# CloudF4Block_MicroPython.net
KiCad netlist of a schematic drawn in Altium Designer
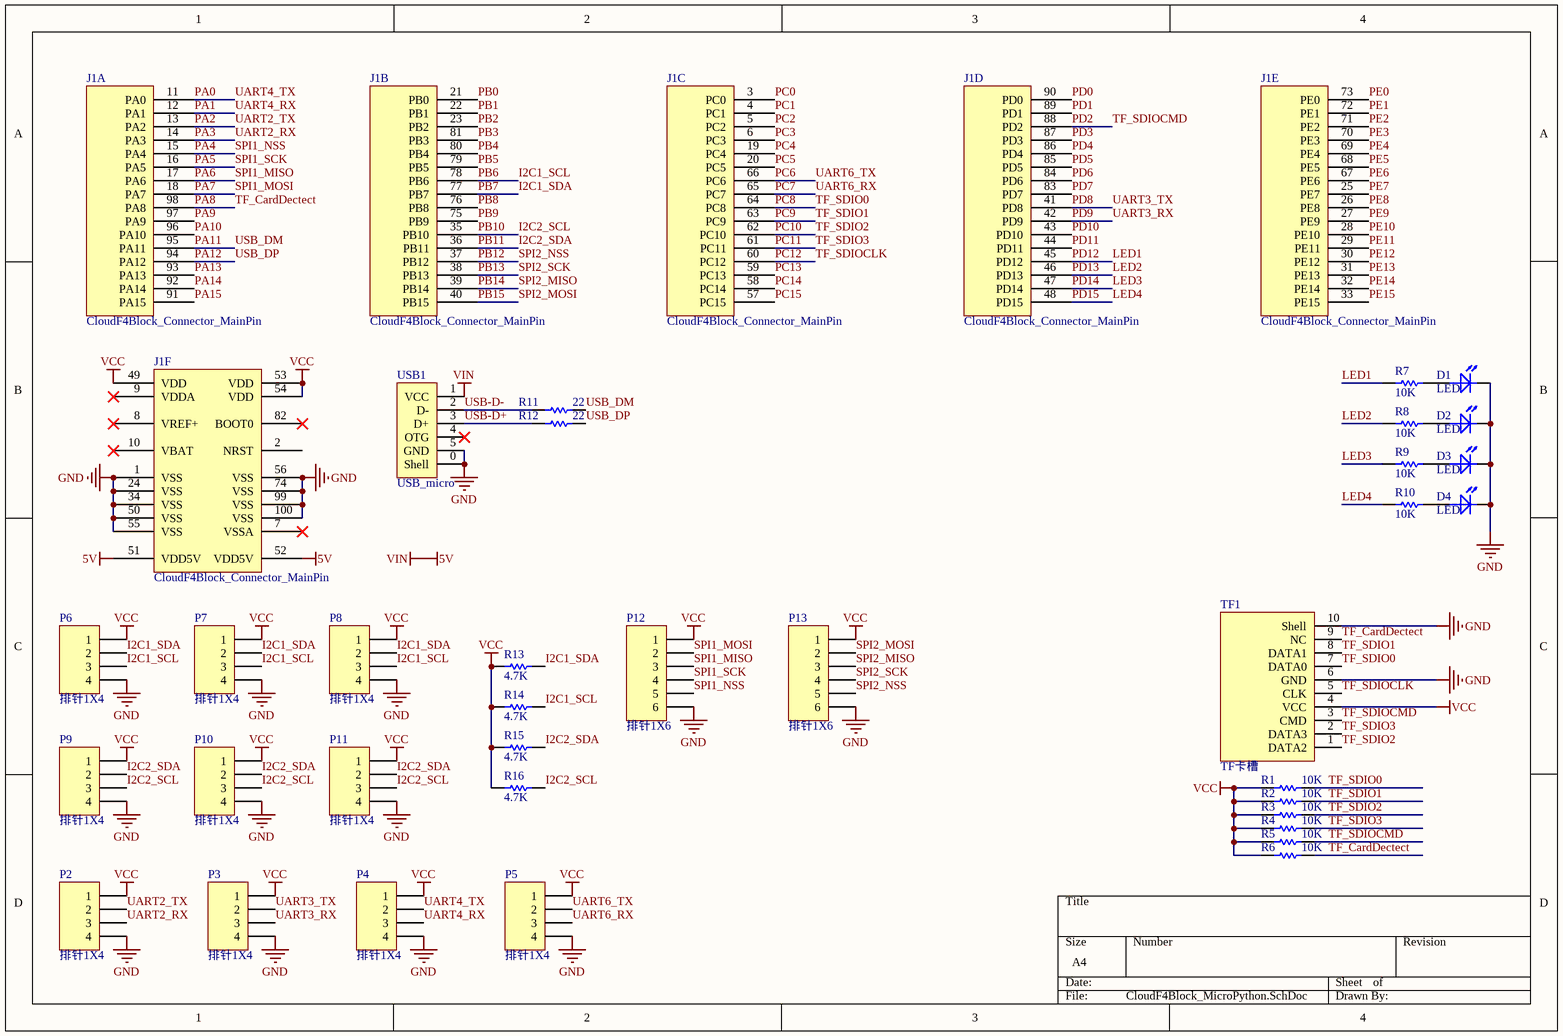
[diagram p0: CloudF4Block_MicroPython.SchDoc]

(export (version "E")
  (design (tool "Eeschema 10.0.6"))
  (components
    (comp (ref "D1")
      (value "LED")
      (footprint "0603LED_RED")
      (libsource (lib "Cloud_AD_Integrated") (part "LED"))
    )
    (comp (ref "D2")
      (value "LED")
      (footprint "0603LED_GREEN")
      (libsource (lib "Cloud_AD_Integrated") (part "LED"))
    )
    (comp (ref "D3")
      (value "LED")
      (footprint "0603LED_ORANGE")
      (libsource (lib "Cloud_AD_Integrated") (part "LED"))
    )
    (comp (ref "D4")
      (value "LED")
      (footprint "0603LED_YELLOW")
      (libsource (lib "Cloud_AD_Integrated") (part "LED"))
    )
    (comp (ref "J1")
      (value "CloudF4Block_Connector_MainPin")
      (footprint "CloudF4BlockConnector")
      (libsource (lib "Cloud_AD_Integrated") (part "CloudF4Block_Connector_MainPin"))
    )
    (comp (ref "P2")
      (value "排针1X4")
      (footprint "IDC1x4-2.54")
      (libsource (lib "Cloud_AD_Integrated") (part "排针1X4"))
    )
    (comp (ref "P3")
      (value "排针1X4")
      (footprint "IDC1x4-2.54")
      (libsource (lib "Cloud_AD_Integrated") (part "排针1X4"))
    )
    (comp (ref "P4")
      (value "排针1X4")
      (footprint "IDC1x4-2.54")
      (libsource (lib "Cloud_AD_Integrated") (part "排针1X4"))
    )
    (comp (ref "P5")
      (value "排针1X4")
      (footprint "IDC1x4-2.54")
      (libsource (lib "Cloud_AD_Integrated") (part "排针1X4"))
    )
    (comp (ref "P6")
      (value "排针1X4")
      (footprint "IDC1x4-2.54")
      (libsource (lib "Cloud_AD_Integrated") (part "排针1X4"))
    )
    (comp (ref "P7")
      (value "排针1X4")
      (footprint "IDC1x4-2.54")
      (libsource (lib "Cloud_AD_Integrated") (part "排针1X4"))
    )
    (comp (ref "P8")
      (value "排针1X4")
      (footprint "IDC1x4-2.54")
      (libsource (lib "Cloud_AD_Integrated") (part "排针1X4"))
    )
    (comp (ref "P9")
      (value "排针1X4")
      (footprint "IDC1x4-2.54")
      (libsource (lib "Cloud_AD_Integrated") (part "排针1X4"))
    )
    (comp (ref "P10")
      (value "排针1X4")
      (footprint "IDC1x4-2.54")
      (libsource (lib "Cloud_AD_Integrated") (part "排针1X4"))
    )
    (comp (ref "P11")
      (value "排针1X4")
      (footprint "IDC1x4-2.54")
      (libsource (lib "Cloud_AD_Integrated") (part "排针1X4"))
    )
    (comp (ref "P12")
      (value "排针1X6")
      (footprint "IDC1x6-2.54")
      (libsource (lib "Cloud_AD_Integrated") (part "排针1X6"))
    )
    (comp (ref "P13")
      (value "排针1X6")
      (footprint "IDC1x6-2.54")
      (libsource (lib "Cloud_AD_Integrated") (part "排针1X6"))
    )
    (comp (ref "R1")
      (value "10K")
      (footprint "R-0603")
      (fields (field (name "Comment") "RES"))
      (libsource (lib "Cloud_AD_Integrated") (part "RES"))
    )
    (comp (ref "R2")
      (value "10K")
      (footprint "R-0603")
      (fields (field (name "Comment") "RES"))
      (libsource (lib "Cloud_AD_Integrated") (part "RES"))
    )
    (comp (ref "R3")
      (value "10K")
      (footprint "R-0603")
      (fields (field (name "Comment") "RES"))
      (libsource (lib "Cloud_AD_Integrated") (part "RES"))
    )
    (comp (ref "R4")
      (value "10K")
      (footprint "R-0603")
      (fields (field (name "Comment") "RES"))
      (libsource (lib "Cloud_AD_Integrated") (part "RES"))
    )
    (comp (ref "R5")
      (value "10K")
      (footprint "R-0603")
      (fields (field (name "Comment") "RES"))
      (libsource (lib "Cloud_AD_Integrated") (part "RES"))
    )
    (comp (ref "R6")
      (value "10K")
      (footprint "R-0603")
      (fields (field (name "Comment") "RES"))
      (libsource (lib "Cloud_AD_Integrated") (part "RES"))
    )
    (comp (ref "R7")
      (value "10K")
      (footprint "R-0603")
      (fields (field (name "Comment") "RES"))
      (libsource (lib "Cloud_AD_Integrated") (part "RES"))
    )
    (comp (ref "R8")
      (value "10K")
      (footprint "R-0603")
      (fields (field (name "Comment") "RES"))
      (libsource (lib "Cloud_AD_Integrated") (part "RES"))
    )
    (comp (ref "R9")
      (value "10K")
      (footprint "R-0603")
      (fields (field (name "Comment") "RES"))
      (libsource (lib "Cloud_AD_Integrated") (part "RES"))
    )
    (comp (ref "R10")
      (value "10K")
      (footprint "R-0603")
      (fields (field (name "Comment") "RES"))
      (libsource (lib "Cloud_AD_Integrated") (part "RES"))
    )
    (comp (ref "R11")
      (value "22")
      (footprint "R-0603")
      (fields (field (name "Comment") "RES"))
      (libsource (lib "Cloud_AD_Integrated") (part "RES"))
    )
    (comp (ref "R12")
      (value "22")
      (footprint "R-0603")
      (fields (field (name "Comment") "RES"))
      (libsource (lib "Cloud_AD_Integrated") (part "RES"))
    )
    (comp (ref "R13")
      (value "4.7K")
      (footprint "R-0603")
      (fields (field (name "Comment") "RES"))
      (libsource (lib "Cloud_AD_Integrated") (part "RES"))
    )
    (comp (ref "R14")
      (value "4.7K")
      (footprint "R-0603")
      (fields (field (name "Comment") "RES"))
      (libsource (lib "Cloud_AD_Integrated") (part "RES"))
    )
    (comp (ref "R15")
      (value "4.7K")
      (footprint "R-0603")
      (fields (field (name "Comment") "RES"))
      (libsource (lib "Cloud_AD_Integrated") (part "RES"))
    )
    (comp (ref "R16")
      (value "4.7K")
      (footprint "R-0603")
      (fields (field (name "Comment") "RES"))
      (libsource (lib "Cloud_AD_Integrated") (part "RES"))
    )
    (comp (ref "TF1")
      (value "TF卡槽")
      (footprint "TF_Card")
      (libsource (lib "Cloud_AD_Integrated") (part "TF卡槽"))
    )
    (comp (ref "USB1")
      (value "USB_micro")
      (footprint "USB-MICRO")
      (libsource (lib "Cloud_AD_Integrated") (part "USB_micro"))
    )
  )
  (nets
    (net (code "1") (name "/I2C1_SCL") (class "Default")
      (node (ref "J1") (pin "78") (pinfunction "PB6_78") (pintype "passive"))
      (node (ref "P6") (pin "3") (pinfunction "3_3") (pintype "passive"))
      (node (ref "P7") (pin "3") (pinfunction "3_3") (pintype "passive"))
      (node (ref "P8") (pin "3") (pinfunction "3_3") (pintype "passive"))
      (node (ref "R14") (pin "2") (pinfunction "2_2") (pintype "passive"))
    )
    (net (code "2") (name "/I2C1_SDA") (class "Default")
      (node (ref "J1") (pin "77") (pinfunction "PB7_77") (pintype "passive"))
      (node (ref "P6") (pin "2") (pinfunction "2_2") (pintype "passive"))
      (node (ref "P7") (pin "2") (pinfunction "2_2") (pintype "passive"))
      (node (ref "P8") (pin "2") (pinfunction "2_2") (pintype "passive"))
      (node (ref "R13") (pin "2") (pinfunction "2_2") (pintype "passive"))
    )
    (net (code "3") (name "/I2C2_SCL") (class "Default")
      (node (ref "J1") (pin "35") (pinfunction "PB10_35") (pintype "passive"))
      (node (ref "P10") (pin "3") (pinfunction "3_3") (pintype "passive"))
      (node (ref "P11") (pin "3") (pinfunction "3_3") (pintype "passive"))
      (node (ref "P9") (pin "3") (pinfunction "3_3") (pintype "passive"))
      (node (ref "R16") (pin "2") (pinfunction "2_2") (pintype "passive"))
    )
    (net (code "4") (name "/I2C2_SDA") (class "Default")
      (node (ref "J1") (pin "36") (pinfunction "PB11_36") (pintype "passive"))
      (node (ref "P10") (pin "2") (pinfunction "2_2") (pintype "passive"))
      (node (ref "P11") (pin "2") (pinfunction "2_2") (pintype "passive"))
      (node (ref "P9") (pin "2") (pinfunction "2_2") (pintype "passive"))
      (node (ref "R15") (pin "2") (pinfunction "2_2") (pintype "passive"))
    )
    (net (code "5") (name "/LED1") (class "Default")
      (node (ref "J1") (pin "45") (pinfunction "PD12_45") (pintype "passive"))
      (node (ref "R7") (pin "2") (pinfunction "2_2") (pintype "passive"))
    )
    (net (code "6") (name "/LED2") (class "Default")
      (node (ref "J1") (pin "46") (pinfunction "PD13_46") (pintype "passive"))
      (node (ref "R8") (pin "2") (pinfunction "2_2") (pintype "passive"))
    )
    (net (code "7") (name "/LED3") (class "Default")
      (node (ref "J1") (pin "47") (pinfunction "PD14_47") (pintype "passive"))
      (node (ref "R9") (pin "2") (pinfunction "2_2") (pintype "passive"))
    )
    (net (code "8") (name "/LED4") (class "Default")
      (node (ref "J1") (pin "48") (pinfunction "PD15_48") (pintype "passive"))
      (node (ref "R10") (pin "2") (pinfunction "2_2") (pintype "passive"))
    )
    (net (code "9") (name "/PA0") (class "Default")
      (node (ref "J1") (pin "11") (pinfunction "PA0_11") (pintype "passive"))
      (node (ref "P4") (pin "2") (pinfunction "2_2") (pintype "passive"))
    )
    (net (code "10") (name "/PA1") (class "Default")
      (node (ref "J1") (pin "12") (pinfunction "PA1_12") (pintype "passive"))
      (node (ref "P4") (pin "3") (pinfunction "3_3") (pintype "passive"))
    )
    (net (code "11") (name "/PA2") (class "Default")
      (node (ref "J1") (pin "13") (pinfunction "PA2_13") (pintype "passive"))
      (node (ref "P2") (pin "2") (pinfunction "2_2") (pintype "passive"))
    )
    (net (code "12") (name "/PA3") (class "Default")
      (node (ref "J1") (pin "14") (pinfunction "PA3_14") (pintype "passive"))
      (node (ref "P2") (pin "3") (pinfunction "3_3") (pintype "passive"))
    )
    (net (code "13") (name "/PA4") (class "Default")
      (node (ref "J1") (pin "15") (pinfunction "PA4_15") (pintype "passive"))
      (node (ref "P12") (pin "5") (pinfunction "5_5") (pintype "passive"))
    )
    (net (code "14") (name "/PA5") (class "Default")
      (node (ref "J1") (pin "16") (pinfunction "PA5_16") (pintype "passive"))
      (node (ref "P12") (pin "4") (pinfunction "4_4") (pintype "passive"))
    )
    (net (code "15") (name "/PA6") (class "Default")
      (node (ref "J1") (pin "17") (pinfunction "PA6_17") (pintype "passive"))
      (node (ref "P12") (pin "3") (pinfunction "3_3") (pintype "passive"))
    )
    (net (code "16") (name "/PA7") (class "Default")
      (node (ref "J1") (pin "18") (pinfunction "PA7_18") (pintype "passive"))
      (node (ref "P12") (pin "2") (pinfunction "2_2") (pintype "passive"))
    )
    (net (code "17") (name "/PA8") (class "Default")
      (node (ref "J1") (pin "98") (pinfunction "PA8_98") (pintype "passive"))
      (node (ref "R6") (pin "2") (pinfunction "2_2") (pintype "passive"))
      (node (ref "TF1") (pin "9") (pinfunction "NC_9") (pintype "passive"))
    )
    (net (code "18") (name "/PA9") (class "Default")
      (node (ref "J1") (pin "97") (pinfunction "PA9_97") (pintype "passive"))
    )
    (net (code "19") (name "/PA10") (class "Default")
      (node (ref "J1") (pin "96") (pinfunction "PA10_96") (pintype "passive"))
    )
    (net (code "20") (name "/PA11") (class "Default")
      (node (ref "J1") (pin "95") (pinfunction "PA11_95") (pintype "passive"))
      (node (ref "R11") (pin "1") (pinfunction "1_1") (pintype "passive"))
    )
    (net (code "21") (name "/PA12") (class "Default")
      (node (ref "J1") (pin "94") (pinfunction "PA12_94") (pintype "passive"))
      (node (ref "R12") (pin "1") (pinfunction "1_1") (pintype "passive"))
    )
    (net (code "22") (name "/PA13") (class "Default")
      (node (ref "J1") (pin "93") (pinfunction "PA13_93") (pintype "passive"))
    )
    (net (code "23") (name "/PA14") (class "Default")
      (node (ref "J1") (pin "92") (pinfunction "PA14_92") (pintype "passive"))
    )
    (net (code "24") (name "/PA15") (class "Default")
      (node (ref "J1") (pin "91") (pinfunction "PA15_91") (pintype "passive"))
    )
    (net (code "25") (name "/PB0") (class "Default")
      (node (ref "J1") (pin "21") (pinfunction "PB0_21") (pintype "passive"))
    )
    (net (code "26") (name "/PB1") (class "Default")
      (node (ref "J1") (pin "22") (pinfunction "PB1_22") (pintype "passive"))
    )
    (net (code "27") (name "/PB2") (class "Default")
      (node (ref "J1") (pin "23") (pinfunction "PB2_23") (pintype "passive"))
    )
    (net (code "28") (name "/PB3") (class "Default")
      (node (ref "J1") (pin "81") (pinfunction "PB3_81") (pintype "passive"))
    )
    (net (code "29") (name "/PB4") (class "Default")
      (node (ref "J1") (pin "80") (pinfunction "PB4_80") (pintype "passive"))
    )
    (net (code "30") (name "/PB5") (class "Default")
      (node (ref "J1") (pin "79") (pinfunction "PB5_79") (pintype "passive"))
    )
    (net (code "31") (name "/PB8") (class "Default")
      (node (ref "J1") (pin "76") (pinfunction "PB8_76") (pintype "passive"))
    )
    (net (code "32") (name "/PB9") (class "Default")
      (node (ref "J1") (pin "75") (pinfunction "PB9_75") (pintype "passive"))
    )
    (net (code "33") (name "/PB12") (class "Default")
      (node (ref "J1") (pin "37") (pinfunction "PB12_37") (pintype "passive"))
      (node (ref "P13") (pin "5") (pinfunction "5_5") (pintype "passive"))
    )
    (net (code "34") (name "/PB13") (class "Default")
      (node (ref "J1") (pin "38") (pinfunction "PB13_38") (pintype "passive"))
      (node (ref "P13") (pin "4") (pinfunction "4_4") (pintype "passive"))
    )
    (net (code "35") (name "/PB14") (class "Default")
      (node (ref "J1") (pin "39") (pinfunction "PB14_39") (pintype "passive"))
      (node (ref "P13") (pin "3") (pinfunction "3_3") (pintype "passive"))
    )
    (net (code "36") (name "/PB15") (class "Default")
      (node (ref "J1") (pin "40") (pinfunction "PB15_40") (pintype "passive"))
      (node (ref "P13") (pin "2") (pinfunction "2_2") (pintype "passive"))
    )
    (net (code "37") (name "/PC0") (class "Default")
      (node (ref "J1") (pin "3") (pinfunction "PC0_3") (pintype "passive"))
    )
    (net (code "38") (name "/PC1") (class "Default")
      (node (ref "J1") (pin "4") (pinfunction "PC1_4") (pintype "passive"))
    )
    (net (code "39") (name "/PC2") (class "Default")
      (node (ref "J1") (pin "5") (pinfunction "PC2_5") (pintype "passive"))
    )
    (net (code "40") (name "/PC3") (class "Default")
      (node (ref "J1") (pin "6") (pinfunction "PC3_6") (pintype "passive"))
    )
    (net (code "41") (name "/PC4") (class "Default")
      (node (ref "J1") (pin "19") (pinfunction "PC4_19") (pintype "passive"))
    )
    (net (code "42") (name "/PC5") (class "Default")
      (node (ref "J1") (pin "20") (pinfunction "PC5_20") (pintype "passive"))
    )
    (net (code "43") (name "/PC6") (class "Default")
      (node (ref "J1") (pin "66") (pinfunction "PC6_66") (pintype "passive"))
      (node (ref "P5") (pin "2") (pinfunction "2_2") (pintype "passive"))
    )
    (net (code "44") (name "/PC7") (class "Default")
      (node (ref "J1") (pin "65") (pinfunction "PC7_65") (pintype "passive"))
      (node (ref "P5") (pin "3") (pinfunction "3_3") (pintype "passive"))
    )
    (net (code "45") (name "/PC8") (class "Default")
      (node (ref "J1") (pin "64") (pinfunction "PC8_64") (pintype "passive"))
      (node (ref "R1") (pin "2") (pinfunction "2_2") (pintype "passive"))
      (node (ref "TF1") (pin "7") (pinfunction "DATA0_7") (pintype "passive"))
    )
    (net (code "46") (name "/PC9") (class "Default")
      (node (ref "J1") (pin "63") (pinfunction "PC9_63") (pintype "passive"))
      (node (ref "R2") (pin "2") (pinfunction "2_2") (pintype "passive"))
      (node (ref "TF1") (pin "8") (pinfunction "DATA1_8") (pintype "passive"))
    )
    (net (code "47") (name "/PC10") (class "Default")
      (node (ref "J1") (pin "62") (pinfunction "PC10_62") (pintype "passive"))
      (node (ref "R3") (pin "2") (pinfunction "2_2") (pintype "passive"))
      (node (ref "TF1") (pin "1") (pinfunction "DATA2_1") (pintype "passive"))
    )
    (net (code "48") (name "/PC11") (class "Default")
      (node (ref "J1") (pin "61") (pinfunction "PC11_61") (pintype "passive"))
      (node (ref "R4") (pin "2") (pinfunction "2_2") (pintype "passive"))
      (node (ref "TF1") (pin "2") (pinfunction "DATA3_2") (pintype "passive"))
    )
    (net (code "49") (name "/PC12") (class "Default")
      (node (ref "J1") (pin "60") (pinfunction "PC12_60") (pintype "passive"))
      (node (ref "TF1") (pin "5") (pinfunction "CLK_5") (pintype "passive"))
    )
    (net (code "50") (name "/PC13") (class "Default")
      (node (ref "J1") (pin "59") (pinfunction "PC13_59") (pintype "passive"))
    )
    (net (code "51") (name "/PC14") (class "Default")
      (node (ref "J1") (pin "58") (pinfunction "PC14_58") (pintype "passive"))
    )
    (net (code "52") (name "/PC15") (class "Default")
      (node (ref "J1") (pin "57") (pinfunction "PC15_57") (pintype "passive"))
    )
    (net (code "53") (name "/PD0") (class "Default")
      (node (ref "J1") (pin "90") (pinfunction "PD0_90") (pintype "passive"))
    )
    (net (code "54") (name "/PD1") (class "Default")
      (node (ref "J1") (pin "89") (pinfunction "PD1_89") (pintype "passive"))
    )
    (net (code "55") (name "/PD2") (class "Default")
      (node (ref "J1") (pin "88") (pinfunction "PD2_88") (pintype "passive"))
      (node (ref "R5") (pin "2") (pinfunction "2_2") (pintype "passive"))
      (node (ref "TF1") (pin "3") (pinfunction "CMD_3") (pintype "passive"))
    )
    (net (code "56") (name "/PD3") (class "Default")
      (node (ref "J1") (pin "87") (pinfunction "PD3_87") (pintype "passive"))
    )
    (net (code "57") (name "/PD4") (class "Default")
      (node (ref "J1") (pin "86") (pinfunction "PD4_86") (pintype "passive"))
    )
    (net (code "58") (name "/PD5") (class "Default")
      (node (ref "J1") (pin "85") (pinfunction "PD5_85") (pintype "passive"))
    )
    (net (code "59") (name "/PD6") (class "Default")
      (node (ref "J1") (pin "84") (pinfunction "PD6_84") (pintype "passive"))
    )
    (net (code "60") (name "/PD7") (class "Default")
      (node (ref "J1") (pin "83") (pinfunction "PD7_83") (pintype "passive"))
    )
    (net (code "61") (name "/PD8") (class "Default")
      (node (ref "J1") (pin "41") (pinfunction "PD8_41") (pintype "passive"))
      (node (ref "P3") (pin "2") (pinfunction "2_2") (pintype "passive"))
    )
    (net (code "62") (name "/PD9") (class "Default")
      (node (ref "J1") (pin "42") (pinfunction "PD9_42") (pintype "passive"))
      (node (ref "P3") (pin "3") (pinfunction "3_3") (pintype "passive"))
    )
    (net (code "63") (name "/PD10") (class "Default")
      (node (ref "J1") (pin "43") (pinfunction "PD10_43") (pintype "passive"))
    )
    (net (code "64") (name "/PD11") (class "Default")
      (node (ref "J1") (pin "44") (pinfunction "PD11_44") (pintype "passive"))
    )
    (net (code "65") (name "/PE0") (class "Default")
      (node (ref "J1") (pin "73") (pinfunction "PE0_73") (pintype "passive"))
    )
    (net (code "66") (name "/PE1") (class "Default")
      (node (ref "J1") (pin "72") (pinfunction "PE1_72") (pintype "passive"))
    )
    (net (code "67") (name "/PE2") (class "Default")
      (node (ref "J1") (pin "71") (pinfunction "PE2_71") (pintype "passive"))
    )
    (net (code "68") (name "/PE3") (class "Default")
      (node (ref "J1") (pin "70") (pinfunction "PE3_70") (pintype "passive"))
    )
    (net (code "69") (name "/PE4") (class "Default")
      (node (ref "J1") (pin "69") (pinfunction "PE4_69") (pintype "passive"))
    )
    (net (code "70") (name "/PE5") (class "Default")
      (node (ref "J1") (pin "68") (pinfunction "PE5_68") (pintype "passive"))
    )
    (net (code "71") (name "/PE6") (class "Default")
      (node (ref "J1") (pin "67") (pinfunction "PE6_67") (pintype "passive"))
    )
    (net (code "72") (name "/PE7") (class "Default")
      (node (ref "J1") (pin "25") (pinfunction "PE7_25") (pintype "passive"))
    )
    (net (code "73") (name "/PE8") (class "Default")
      (node (ref "J1") (pin "26") (pinfunction "PE8_26") (pintype "passive"))
    )
    (net (code "74") (name "/PE9") (class "Default")
      (node (ref "J1") (pin "27") (pinfunction "PE9_27") (pintype "passive"))
    )
    (net (code "75") (name "/PE10") (class "Default")
      (node (ref "J1") (pin "28") (pinfunction "PE10_28") (pintype "passive"))
    )
    (net (code "76") (name "/PE11") (class "Default")
      (node (ref "J1") (pin "29") (pinfunction "PE11_29") (pintype "passive"))
    )
    (net (code "77") (name "/PE12") (class "Default")
      (node (ref "J1") (pin "30") (pinfunction "PE12_30") (pintype "passive"))
    )
    (net (code "78") (name "/PE13") (class "Default")
      (node (ref "J1") (pin "31") (pinfunction "PE13_31") (pintype "passive"))
    )
    (net (code "79") (name "/PE14") (class "Default")
      (node (ref "J1") (pin "32") (pinfunction "PE14_32") (pintype "passive"))
    )
    (net (code "80") (name "/PE15") (class "Default")
      (node (ref "J1") (pin "33") (pinfunction "PE15_33") (pintype "passive"))
    )
    (net (code "81") (name "/USB-D+") (class "Default")
      (node (ref "R12") (pin "2") (pinfunction "2_2") (pintype "passive"))
      (node (ref "USB1") (pin "3") (pinfunction "D+_3") (pintype "passive"))
    )
    (net (code "82") (name "/USB-D-") (class "Default")
      (node (ref "R11") (pin "2") (pinfunction "2_2") (pintype "passive"))
      (node (ref "USB1") (pin "2") (pinfunction "D-_2") (pintype "passive"))
    )
    (net (code "83") (name "5V") (class "Default")
      (node (ref "J1") (pin "51") (pinfunction "VDD5V_51") (pintype "passive"))
      (node (ref "J1") (pin "52") (pinfunction "VDD5V_52") (pintype "passive"))
      (node (ref "USB1") (pin "1") (pinfunction "VCC_1") (pintype "passive"))
    )
    (net (code "84") (name "GND") (class "Default")
      (node (ref "D1") (pin "2") (pinfunction "K_2") (pintype "passive"))
      (node (ref "D2") (pin "2") (pinfunction "K_2") (pintype "passive"))
      (node (ref "D3") (pin "2") (pinfunction "K_2") (pintype "passive"))
      (node (ref "D4") (pin "2") (pinfunction "K_2") (pintype "passive"))
      (node (ref "J1") (pin "1") (pinfunction "VSS_1") (pintype "passive"))
      (node (ref "J1") (pin "100") (pinfunction "VSS_100") (pintype "passive"))
      (node (ref "J1") (pin "24") (pinfunction "VSS_24") (pintype "passive"))
      (node (ref "J1") (pin "34") (pinfunction "VSS_34") (pintype "passive"))
      (node (ref "J1") (pin "50") (pinfunction "VSS_50") (pintype "passive"))
      (node (ref "J1") (pin "55") (pinfunction "VSS_55") (pintype "passive"))
      (node (ref "J1") (pin "56") (pinfunction "VSS_56") (pintype "passive"))
      (node (ref "J1") (pin "74") (pinfunction "VSS_74") (pintype "passive"))
      (node (ref "J1") (pin "99") (pinfunction "VSS_99") (pintype "passive"))
      (node (ref "P10") (pin "4") (pinfunction "4_4") (pintype "passive"))
      (node (ref "P11") (pin "4") (pinfunction "4_4") (pintype "passive"))
      (node (ref "P12") (pin "6") (pinfunction "6_6") (pintype "passive"))
      (node (ref "P13") (pin "6") (pinfunction "6_6") (pintype "passive"))
      (node (ref "P2") (pin "4") (pinfunction "4_4") (pintype "passive"))
      (node (ref "P3") (pin "4") (pinfunction "4_4") (pintype "passive"))
      (node (ref "P4") (pin "4") (pinfunction "4_4") (pintype "passive"))
      (node (ref "P5") (pin "4") (pinfunction "4_4") (pintype "passive"))
      (node (ref "P6") (pin "4") (pinfunction "4_4") (pintype "passive"))
      (node (ref "P7") (pin "4") (pinfunction "4_4") (pintype "passive"))
      (node (ref "P8") (pin "4") (pinfunction "4_4") (pintype "passive"))
      (node (ref "P9") (pin "4") (pinfunction "4_4") (pintype "passive"))
      (node (ref "TF1") (pin "10") (pinfunction "Shell_10") (pintype "passive"))
      (node (ref "TF1") (pin "6") (pinfunction "GND_6") (pintype "passive"))
      (node (ref "USB1") (pin "0") (pinfunction "Shell_0") (pintype "passive"))
      (node (ref "USB1") (pin "5") (pinfunction "GND_5") (pintype "passive"))
    )
    (net (code "85") (name "Net-(D1-A)") (class "Default")
      (node (ref "D1") (pin "1") (pinfunction "A_1") (pintype "passive"))
      (node (ref "R7") (pin "1") (pinfunction "1_1") (pintype "passive"))
    )
    (net (code "86") (name "Net-(D2-A)") (class "Default")
      (node (ref "D2") (pin "1") (pinfunction "A_1") (pintype "passive"))
      (node (ref "R8") (pin "1") (pinfunction "1_1") (pintype "passive"))
    )
    (net (code "87") (name "Net-(D3-A)") (class "Default")
      (node (ref "D3") (pin "1") (pinfunction "A_1") (pintype "passive"))
      (node (ref "R9") (pin "1") (pinfunction "1_1") (pintype "passive"))
    )
    (net (code "88") (name "Net-(D4-A)") (class "Default")
      (node (ref "D4") (pin "1") (pinfunction "A_1") (pintype "passive"))
      (node (ref "R10") (pin "1") (pinfunction "1_1") (pintype "passive"))
    )
    (net (code "89") (name "VCC") (class "Default")
      (node (ref "J1") (pin "49") (pinfunction "VDD_49") (pintype "passive"))
      (node (ref "J1") (pin "53") (pinfunction "VDD_53") (pintype "passive"))
      (node (ref "J1") (pin "54") (pinfunction "VDD_54") (pintype "passive"))
      (node (ref "P10") (pin "1") (pinfunction "1_1") (pintype "passive"))
      (node (ref "P11") (pin "1") (pinfunction "1_1") (pintype "passive"))
      (node (ref "P12") (pin "1") (pinfunction "1_1") (pintype "passive"))
      (node (ref "P13") (pin "1") (pinfunction "1_1") (pintype "passive"))
      (node (ref "P2") (pin "1") (pinfunction "1_1") (pintype "passive"))
      (node (ref "P3") (pin "1") (pinfunction "1_1") (pintype "passive"))
      (node (ref "P4") (pin "1") (pinfunction "1_1") (pintype "passive"))
      (node (ref "P5") (pin "1") (pinfunction "1_1") (pintype "passive"))
      (node (ref "P6") (pin "1") (pinfunction "1_1") (pintype "passive"))
      (node (ref "P7") (pin "1") (pinfunction "1_1") (pintype "passive"))
      (node (ref "P8") (pin "1") (pinfunction "1_1") (pintype "passive"))
      (node (ref "P9") (pin "1") (pinfunction "1_1") (pintype "passive"))
      (node (ref "R1") (pin "1") (pinfunction "1_1") (pintype "passive"))
      (node (ref "R13") (pin "1") (pinfunction "1_1") (pintype "passive"))
      (node (ref "R14") (pin "1") (pinfunction "1_1") (pintype "passive"))
      (node (ref "R15") (pin "1") (pinfunction "1_1") (pintype "passive"))
      (node (ref "R16") (pin "1") (pinfunction "1_1") (pintype "passive"))
      (node (ref "R2") (pin "1") (pinfunction "1_1") (pintype "passive"))
      (node (ref "R3") (pin "1") (pinfunction "1_1") (pintype "passive"))
      (node (ref "R4") (pin "1") (pinfunction "1_1") (pintype "passive"))
      (node (ref "R5") (pin "1") (pinfunction "1_1") (pintype "passive"))
      (node (ref "R6") (pin "1") (pinfunction "1_1") (pintype "passive"))
      (node (ref "TF1") (pin "4") (pinfunction "VCC_4") (pintype "passive"))
    )
    (net (code "90") (name "unconnected-(J1F-BOOT0-Pad82)") (class "Default")
      (node (ref "J1") (pin "82") (pinfunction "BOOT0_82") (pintype "passive+no_connect"))
    )
    (net (code "91") (name "unconnected-(J1F-NRST-Pad2)") (class "Default")
      (node (ref "J1") (pin "2") (pinfunction "NRST_2") (pintype "passive"))
    )
    (net (code "92") (name "unconnected-(J1F-VBAT-Pad10)") (class "Default")
      (node (ref "J1") (pin "10") (pinfunction "VBAT_10") (pintype "passive+no_connect"))
    )
    (net (code "93") (name "unconnected-(J1F-VDDA-Pad9)") (class "Default")
      (node (ref "J1") (pin "9") (pinfunction "VDDA_9") (pintype "passive+no_connect"))
    )
    (net (code "94") (name "unconnected-(J1F-VREF+-Pad8)") (class "Default")
      (node (ref "J1") (pin "8") (pinfunction "VREF+_8") (pintype "passive+no_connect"))
    )
    (net (code "95") (name "unconnected-(J1F-VSSA-Pad7)") (class "Default")
      (node (ref "J1") (pin "7") (pinfunction "VSSA_7") (pintype "passive+no_connect"))
    )
    (net (code "96") (name "unconnected-(USB1-OTG-Pad4)") (class "Default")
      (node (ref "USB1") (pin "4") (pinfunction "OTG_4") (pintype "passive+no_connect"))
    )
  )
)
